# relay_board_ssr.net
KiCad netlist of a schematic drawn in EAGLE
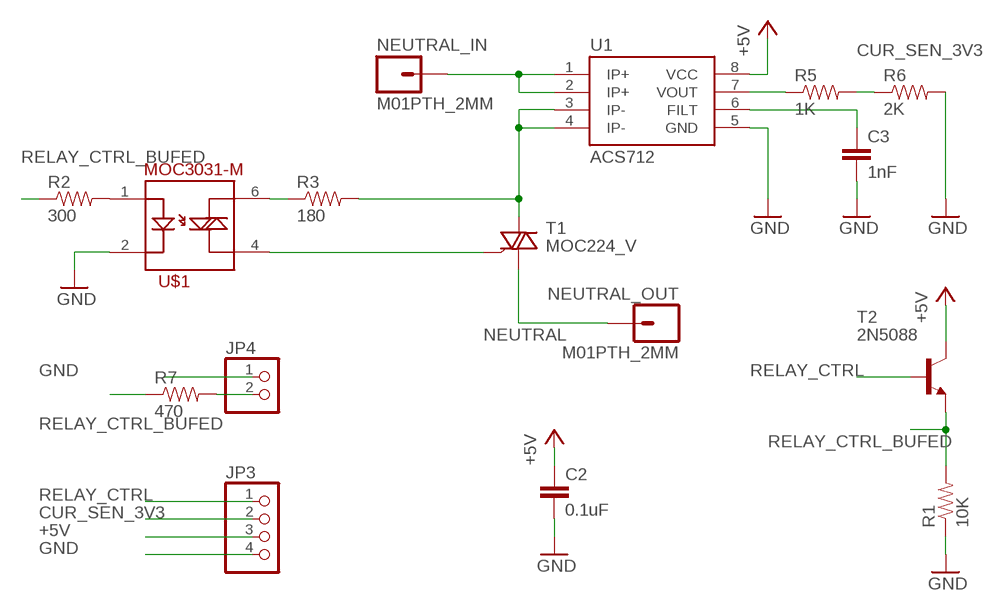
[diagram p0: schematic, sheet 1]

(export (version "E")
  (design (tool "Eeschema 10.0.6"))
  (components
    (comp (ref "C2")
      (value "0.1uF")
      (footprint "eagle-import:CAP-PTH-SMALLEZ")
      (libsource (lib "eagle-import") (part "CAPEZ"))
    )
    (comp (ref "C3")
      (value "1nF")
      (footprint "eagle-import:CAP-PTH-SMALLEZ")
      (libsource (lib "eagle-import") (part "CAPEZ"))
    )
    (comp (ref "JP3")
      (value "PINHD-1X4")
      (footprint "eagle-import:1X04")
      (libsource (lib "eagle-import") (part "PINHD-1X4"))
    )
    (comp (ref "JP4")
      (value "PINHD-1X2")
      (footprint "eagle-import:1X02")
      (libsource (lib "eagle-import") (part "PINHD-1X2"))
    )
    (comp (ref "NEUTRAL_IN")
      (value "M01PTH_2MM")
      (footprint "eagle-import:1X01_2MM")
      (libsource (lib "eagle-import") (part "M01PTH_2MM"))
    )
    (comp (ref "NEUTRAL_OUT")
      (value "M01PTH_2MM")
      (footprint "eagle-import:1X01_2MM")
      (libsource (lib "eagle-import") (part "M01PTH_2MM"))
    )
    (comp (ref "R1")
      (value "10K")
      (footprint "eagle-import:AXIAL-0.1")
      (libsource (lib "eagle-import") (part "10KOHM1/6W5%(PTH)VERTICAL"))
    )
    (comp (ref "R2")
      (value "300")
      (footprint "eagle-import:AXIAL-0.1")
      (libsource (lib "eagle-import") (part "10KOHM1/6W5%(PTH)VERTICAL"))
    )
    (comp (ref "R3")
      (value "180")
      (footprint "eagle-import:AXIAL-0.1")
      (libsource (lib "eagle-import") (part "10KOHM1/6W5%(PTH)VERTICAL"))
    )
    (comp (ref "R5")
      (value "1K")
      (footprint "eagle-import:AXIAL-0.1")
      (libsource (lib "eagle-import") (part "10KOHM1/6W5%(PTH)VERTICAL"))
    )
    (comp (ref "R6")
      (value "2K")
      (footprint "eagle-import:AXIAL-0.1")
      (libsource (lib "eagle-import") (part "10KOHM1/6W5%(PTH)VERTICAL"))
    )
    (comp (ref "R7")
      (value "470")
      (footprint "eagle-import:AXIAL-0.1")
      (libsource (lib "eagle-import") (part "10KOHM1/6W5%(PTH)VERTICAL"))
    )
    (comp (ref "T1")
      (value "MOC224_V")
      (footprint "eagle-import:TO220-IGO")
      (libsource (lib "eagle-import") (part "BT136MOC224_V"))
    )
    (comp (ref "T2")
      (value "2N5088")
      (footprint "eagle-import:TO92")
      (libsource (lib "eagle-import") (part "2N5088"))
    )
    (comp (ref "U$1")
      (value "MOC3020")
      (footprint "eagle-import:DIL06")
      (libsource (lib "eagle-import") (part "MOC3031-M"))
    )
    (comp (ref "U1")
      (value "ACS712")
      (footprint "eagle-import:SO08")
      (libsource (lib "eagle-import") (part "ACS712"))
    )
  )
  (nets
    (net (code "1") (name "+5V") (class "Default")
      (node (ref "C2") (pin "1") (pinfunction "1_1") (pintype "passive"))
      (node (ref "JP3") (pin "3") (pinfunction "3_3") (pintype "passive"))
      (node (ref "T2") (pin "1") (pinfunction "C_1") (pintype "passive"))
      (node (ref "U1") (pin "8") (pinfunction "VCC_8") (pintype "bidirectional"))
    )
    (net (code "2") (name "/CUR_SEN_3V3") (class "Default")
      (node (ref "JP3") (pin "2") (pinfunction "2_2") (pintype "passive"))
      (node (ref "R5") (pin "P$2") (pinfunction "2_P$2") (pintype "passive"))
      (node (ref "R6") (pin "P$1") (pinfunction "1_P$1") (pintype "passive"))
    )
    (net (code "3") (name "/NEUTRAL") (class "Default")
      (node (ref "NEUTRAL_OUT") (pin "1") (pinfunction "1_1") (pintype "passive"))
      (node (ref "T1") (pin "T1") (pinfunction "A1_T1") (pintype "passive"))
    )
    (net (code "4") (name "/RELAY_CTRL") (class "Default")
      (node (ref "JP3") (pin "1") (pinfunction "1_1") (pintype "passive"))
      (node (ref "T2") (pin "2") (pinfunction "B_2") (pintype "passive"))
    )
    (net (code "5") (name "/RELAY_CTRL_BUFED") (class "Default")
      (node (ref "R1") (pin "P$2") (pinfunction "2_P$2") (pintype "passive"))
      (node (ref "R2") (pin "P$1") (pinfunction "1_P$1") (pintype "passive"))
      (node (ref "R7") (pin "P$1") (pinfunction "1_P$1") (pintype "passive"))
      (node (ref "T2") (pin "3") (pinfunction "E_3") (pintype "passive"))
    )
    (net (code "6") (name "GND") (class "Default")
      (node (ref "C2") (pin "2") (pinfunction "2_2") (pintype "passive"))
      (node (ref "C3") (pin "2") (pinfunction "2_2") (pintype "passive"))
      (node (ref "JP3") (pin "4") (pinfunction "4_4") (pintype "passive"))
      (node (ref "JP4") (pin "1") (pinfunction "1_1") (pintype "passive"))
      (node (ref "R1") (pin "P$1") (pinfunction "1_P$1") (pintype "passive"))
      (node (ref "R6") (pin "P$2") (pinfunction "2_P$2") (pintype "passive"))
      (node (ref "U$1") (pin "2") (pinfunction "2_2") (pintype "bidirectional"))
      (node (ref "U1") (pin "5") (pinfunction "GND_5") (pintype "bidirectional"))
    )
    (net (code "7") (name "Net-(NEUTRAL_IN-Pad1)") (class "Default")
      (node (ref "NEUTRAL_IN") (pin "1") (pinfunction "1_1") (pintype "passive"))
      (node (ref "U1") (pin "1") (pinfunction "IP+_1") (pintype "bidirectional"))
      (node (ref "U1") (pin "2") (pinfunction "IP+_2") (pintype "bidirectional"))
    )
    (net (code "8") (name "Net-(R2-2)") (class "Default")
      (node (ref "R2") (pin "P$2") (pinfunction "2_P$2") (pintype "passive"))
      (node (ref "U$1") (pin "1") (pinfunction "1_1") (pintype "bidirectional"))
    )
    (net (code "9") (name "Net-(R3-1)") (class "Default")
      (node (ref "R3") (pin "P$1") (pinfunction "1_P$1") (pintype "passive"))
      (node (ref "U$1") (pin "6") (pinfunction "6_6") (pintype "bidirectional"))
    )
    (net (code "10") (name "Net-(R3-2)") (class "Default")
      (node (ref "R3") (pin "P$2") (pinfunction "2_P$2") (pintype "passive"))
      (node (ref "T1") (pin "T2") (pinfunction "A2_T2") (pintype "passive"))
      (node (ref "U1") (pin "3") (pinfunction "IP-_3") (pintype "bidirectional"))
      (node (ref "U1") (pin "4") (pinfunction "IP-_4") (pintype "bidirectional"))
    )
    (net (code "11") (name "Net-(R5-1)") (class "Default")
      (node (ref "R5") (pin "P$1") (pinfunction "1_P$1") (pintype "passive"))
      (node (ref "U1") (pin "7") (pinfunction "VOUT_7") (pintype "bidirectional"))
    )
    (net (code "12") (name "Net-(R7-2)") (class "Default")
      (node (ref "JP4") (pin "2") (pinfunction "2_2") (pintype "passive"))
      (node (ref "R7") (pin "P$2") (pinfunction "2_P$2") (pintype "passive"))
    )
    (net (code "13") (name "Net-(T1-G)") (class "Default")
      (node (ref "T1") (pin "GATE") (pinfunction "G_GATE") (pintype "passive"))
      (node (ref "U$1") (pin "4") (pinfunction "4_4") (pintype "bidirectional"))
    )
    (net (code "14") (name "Net-(U1-FILT)") (class "Default")
      (node (ref "C3") (pin "1") (pinfunction "1_1") (pintype "passive"))
      (node (ref "U1") (pin "6") (pinfunction "FILT_6") (pintype "bidirectional"))
    )
  )
)
